# 03_02_MCU_STM32F103.net
KiCad netlist of a schematic drawn in Altium Designer
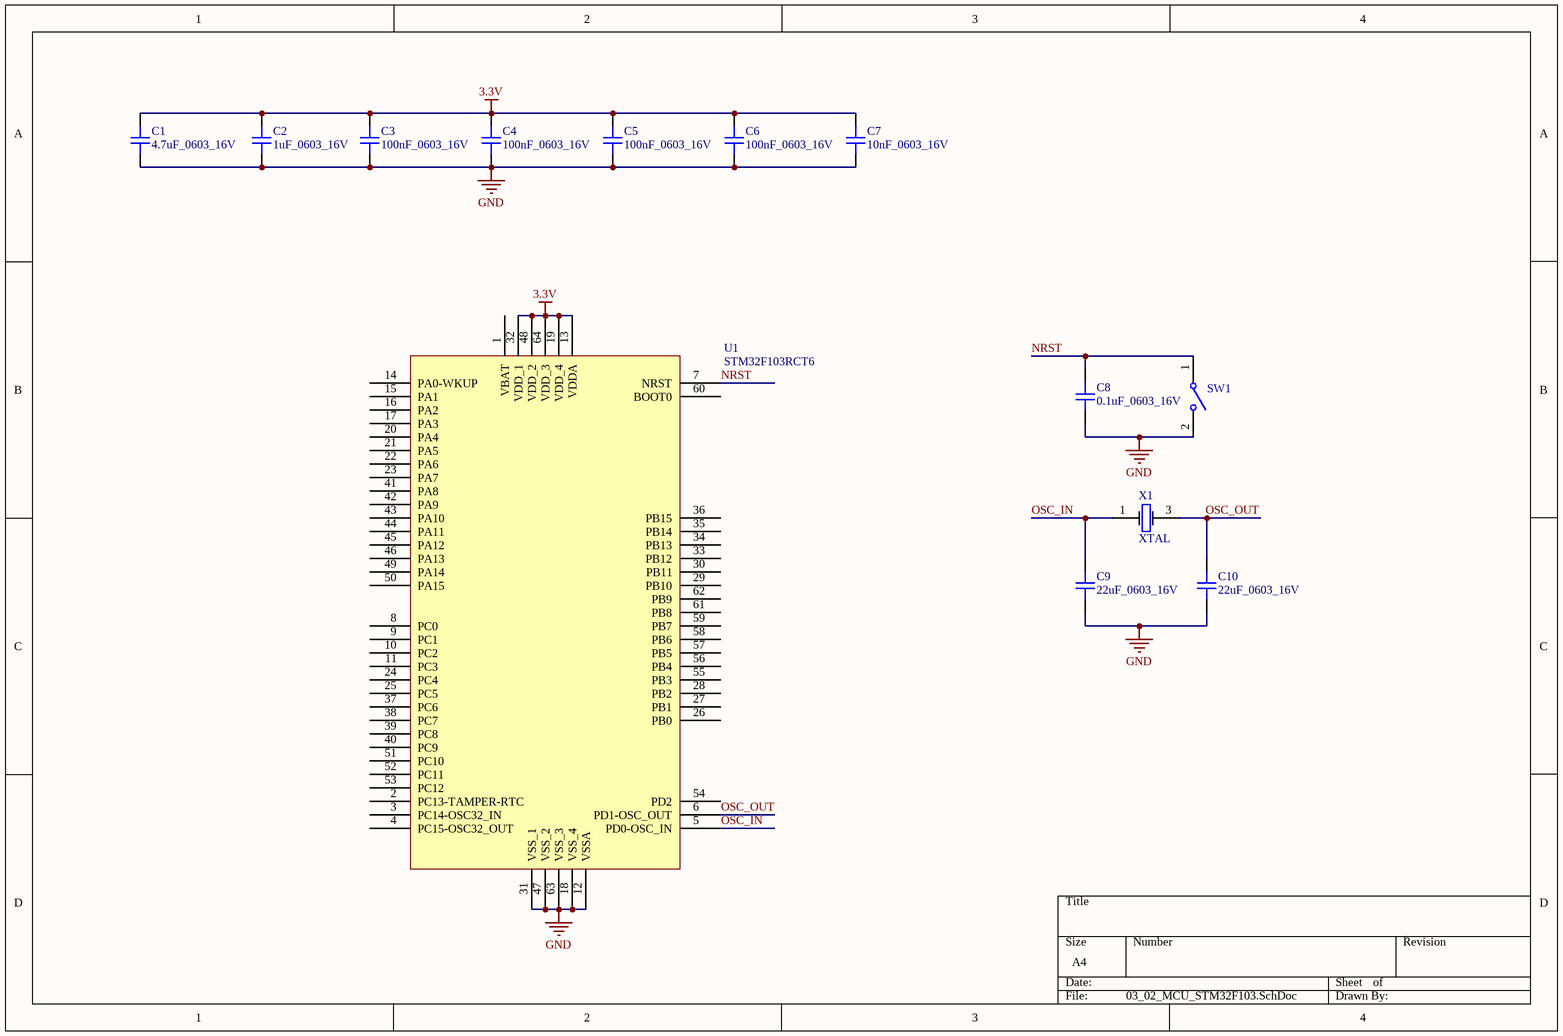
[diagram p0: 03_02_MCU_STM32F103.SchDoc]

(export (version "E")
  (design (tool "Eeschema 10.0.6"))
  (components
    (comp (ref "C1")
      (value "4.7uF_0603_16V")
      (footprint "CAP_0603")
      (description "Capacitor SMD 0603 16V")
      (libsource (lib "Lib-PhilsLab") (part "CAP_0603_16V"))
    )
    (comp (ref "C2")
      (value "1uF_0603_16V")
      (footprint "CAP_0603")
      (description "Capacitor SMD 0603 16V")
      (libsource (lib "Lib-PhilsLab") (part "CAP_0603_16V"))
    )
    (comp (ref "C3")
      (value "100nF_0603_16V")
      (footprint "CAP_0603")
      (description "Capacitor SMD 0603 16V")
      (libsource (lib "Lib-PhilsLab") (part "CAP_0603_16V"))
    )
    (comp (ref "C4")
      (value "100nF_0603_16V")
      (footprint "CAP_0603")
      (description "Capacitor SMD 0603 16V")
      (libsource (lib "Lib-PhilsLab") (part "CAP_0603_16V"))
    )
    (comp (ref "C5")
      (value "100nF_0603_16V")
      (footprint "CAP_0603")
      (description "Capacitor SMD 0603 16V")
      (libsource (lib "Lib-PhilsLab") (part "CAP_0603_16V"))
    )
    (comp (ref "C6")
      (value "100nF_0603_16V")
      (footprint "CAP_0603")
      (description "Capacitor SMD 0603 16V")
      (libsource (lib "Lib-PhilsLab") (part "CAP_0603_16V"))
    )
    (comp (ref "C7")
      (value "10nF_0603_16V")
      (footprint "CAP_0603")
      (description "Capacitor SMD 0603 16V")
      (libsource (lib "Lib-PhilsLab") (part "CAP_0603_16V"))
    )
    (comp (ref "C8")
      (value "0.1uF_0603_16V")
      (footprint "CAP_0603")
      (description "Capacitor SMD 0603 16V")
      (libsource (lib "Lib-PhilsLab") (part "CAP_0603_16V"))
    )
    (comp (ref "C9")
      (value "22uF_0603_16V")
      (footprint "CAP_0603")
      (description "Capacitor SMD 0603 16V")
      (libsource (lib "Lib-PhilsLab") (part "CAP_0603_16V"))
    )
    (comp (ref "C10")
      (value "22uF_0603_16V")
      (footprint "CAP_0603")
      (description "Capacitor SMD 0603 16V")
      (libsource (lib "Lib-PhilsLab") (part "CAP_0603_16V"))
    )
    (comp (ref "SW1")
      (value "434121025816")
      (footprint "WS-TASV_L6W3.8H2.5_4341x10258x6")
      (description "WS-TASV SMT Tact Switch, 12VDC, 50mA, 160g, height 2.5mm")
      (fields (field (name "MANUFACTURER") "Wurth Elektronik"))
      (libsource (lib "Altium_WS-TASV (rev22a)") (part "434121025816"))
    )
    (comp (ref "U1")
      (value "STM32F103RCT6")
      (footprint "STM32F103RCT6")
      (fields (field (name "MFR") "STMicroelectronics"))
      (libsource (lib "Giang's Libs") (part "STM32F103RCT6"))
    )
    (comp (ref "X1") (value "XTAL") (footprint "XTAL 3225") (libsource (lib "MiclsLib") (part "XTAL")))
  )
  (nets
    (net (code "1") (name "/NRST") (class "Default")
      (node (ref "C8") (pin "2") (pinfunction "2_2") (pintype "passive"))
      (node (ref "SW1") (pin "1") (pinfunction "1_1") (pintype "passive"))
      (node (ref "U1") (pin "7") (pinfunction "NRST_7") (pintype "passive"))
    )
    (net (code "2") (name "/OSC_IN") (class "Default")
      (node (ref "C9") (pin "2") (pinfunction "2_2") (pintype "passive"))
      (node (ref "U1") (pin "5") (pinfunction "PD0-OSC_IN_5") (pintype "passive"))
      (node (ref "X1") (pin "1") (pinfunction "8_1") (pintype "passive"))
    )
    (net (code "3") (name "/OSC_OUT") (class "Default")
      (node (ref "C10") (pin "2") (pinfunction "2_2") (pintype "passive"))
      (node (ref "U1") (pin "6") (pinfunction "PD1-OSC_OUT_6") (pintype "passive"))
      (node (ref "X1") (pin "3") (pinfunction "9_3") (pintype "passive"))
    )
    (net (code "4") (name "3.3V") (class "Default")
      (node (ref "C1") (pin "2") (pinfunction "2_2") (pintype "passive"))
      (node (ref "C2") (pin "2") (pinfunction "2_2") (pintype "passive"))
      (node (ref "C3") (pin "2") (pinfunction "2_2") (pintype "passive"))
      (node (ref "C4") (pin "2") (pinfunction "2_2") (pintype "passive"))
      (node (ref "C5") (pin "2") (pinfunction "2_2") (pintype "passive"))
      (node (ref "C6") (pin "2") (pinfunction "2_2") (pintype "passive"))
      (node (ref "C7") (pin "2") (pinfunction "2_2") (pintype "passive"))
      (node (ref "U1") (pin "13") (pinfunction "VDDA_13") (pintype "passive"))
      (node (ref "U1") (pin "19") (pinfunction "VDD_4_19") (pintype "passive"))
      (node (ref "U1") (pin "32") (pinfunction "VDD_1_32") (pintype "passive"))
      (node (ref "U1") (pin "48") (pinfunction "VDD_2_48") (pintype "passive"))
      (node (ref "U1") (pin "64") (pinfunction "VDD_3_64") (pintype "passive"))
    )
    (net (code "5") (name "GND") (class "Default")
      (node (ref "C1") (pin "1") (pinfunction "1_1") (pintype "passive"))
      (node (ref "C10") (pin "1") (pinfunction "1_1") (pintype "passive"))
      (node (ref "C2") (pin "1") (pinfunction "1_1") (pintype "passive"))
      (node (ref "C3") (pin "1") (pinfunction "1_1") (pintype "passive"))
      (node (ref "C4") (pin "1") (pinfunction "1_1") (pintype "passive"))
      (node (ref "C5") (pin "1") (pinfunction "1_1") (pintype "passive"))
      (node (ref "C6") (pin "1") (pinfunction "1_1") (pintype "passive"))
      (node (ref "C7") (pin "1") (pinfunction "1_1") (pintype "passive"))
      (node (ref "C8") (pin "1") (pinfunction "1_1") (pintype "passive"))
      (node (ref "C9") (pin "1") (pinfunction "1_1") (pintype "passive"))
      (node (ref "SW1") (pin "2") (pinfunction "2_2") (pintype "passive"))
      (node (ref "U1") (pin "12") (pinfunction "VSSA_12") (pintype "passive"))
      (node (ref "U1") (pin "18") (pinfunction "VSS_4_18") (pintype "passive"))
      (node (ref "U1") (pin "31") (pinfunction "VSS_1_31") (pintype "passive"))
      (node (ref "U1") (pin "47") (pinfunction "VSS_2_47") (pintype "passive"))
      (node (ref "U1") (pin "63") (pinfunction "VSS_3_63") (pintype "passive"))
    )
    (net (code "6") (name "unconnected-(U1-BOOT0-Pad60)") (class "Default")
      (node (ref "U1") (pin "60") (pinfunction "BOOT0_60") (pintype "passive"))
    )
    (net (code "7") (name "unconnected-(U1-PA0-WKUP-Pad14)") (class "Default")
      (node (ref "U1") (pin "14") (pinfunction "PA0-WKUP_14") (pintype "passive"))
    )
    (net (code "8") (name "unconnected-(U1-PA1-Pad15)") (class "Default")
      (node (ref "U1") (pin "15") (pinfunction "PA1_15") (pintype "passive"))
    )
    (net (code "9") (name "unconnected-(U1-PA2-Pad16)") (class "Default")
      (node (ref "U1") (pin "16") (pinfunction "PA2_16") (pintype "passive"))
    )
    (net (code "10") (name "unconnected-(U1-PA3-Pad17)") (class "Default")
      (node (ref "U1") (pin "17") (pinfunction "PA3_17") (pintype "passive"))
    )
    (net (code "11") (name "unconnected-(U1-PA4-Pad20)") (class "Default")
      (node (ref "U1") (pin "20") (pinfunction "PA4_20") (pintype "passive"))
    )
    (net (code "12") (name "unconnected-(U1-PA5-Pad21)") (class "Default")
      (node (ref "U1") (pin "21") (pinfunction "PA5_21") (pintype "passive"))
    )
    (net (code "13") (name "unconnected-(U1-PA6-Pad22)") (class "Default")
      (node (ref "U1") (pin "22") (pinfunction "PA6_22") (pintype "passive"))
    )
    (net (code "14") (name "unconnected-(U1-PA7-Pad23)") (class "Default")
      (node (ref "U1") (pin "23") (pinfunction "PA7_23") (pintype "passive"))
    )
    (net (code "15") (name "unconnected-(U1-PA8-Pad41)") (class "Default")
      (node (ref "U1") (pin "41") (pinfunction "PA8_41") (pintype "passive"))
    )
    (net (code "16") (name "unconnected-(U1-PA9-Pad42)") (class "Default")
      (node (ref "U1") (pin "42") (pinfunction "PA9_42") (pintype "passive"))
    )
    (net (code "17") (name "unconnected-(U1-PA10-Pad43)") (class "Default")
      (node (ref "U1") (pin "43") (pinfunction "PA10_43") (pintype "passive"))
    )
    (net (code "18") (name "unconnected-(U1-PA11-Pad44)") (class "Default")
      (node (ref "U1") (pin "44") (pinfunction "PA11_44") (pintype "passive"))
    )
    (net (code "19") (name "unconnected-(U1-PA12-Pad45)") (class "Default")
      (node (ref "U1") (pin "45") (pinfunction "PA12_45") (pintype "passive"))
    )
    (net (code "20") (name "unconnected-(U1-PA13-Pad46)") (class "Default")
      (node (ref "U1") (pin "46") (pinfunction "PA13_46") (pintype "passive"))
    )
    (net (code "21") (name "unconnected-(U1-PA14-Pad49)") (class "Default")
      (node (ref "U1") (pin "49") (pinfunction "PA14_49") (pintype "passive"))
    )
    (net (code "22") (name "unconnected-(U1-PA15-Pad50)") (class "Default")
      (node (ref "U1") (pin "50") (pinfunction "PA15_50") (pintype "passive"))
    )
    (net (code "23") (name "unconnected-(U1-PB0-Pad26)") (class "Default")
      (node (ref "U1") (pin "26") (pinfunction "PB0_26") (pintype "passive"))
    )
    (net (code "24") (name "unconnected-(U1-PB1-Pad27)") (class "Default")
      (node (ref "U1") (pin "27") (pinfunction "PB1_27") (pintype "passive"))
    )
    (net (code "25") (name "unconnected-(U1-PB2-Pad28)") (class "Default")
      (node (ref "U1") (pin "28") (pinfunction "PB2_28") (pintype "passive"))
    )
    (net (code "26") (name "unconnected-(U1-PB3-Pad55)") (class "Default")
      (node (ref "U1") (pin "55") (pinfunction "PB3_55") (pintype "passive"))
    )
    (net (code "27") (name "unconnected-(U1-PB4-Pad56)") (class "Default")
      (node (ref "U1") (pin "56") (pinfunction "PB4_56") (pintype "passive"))
    )
    (net (code "28") (name "unconnected-(U1-PB5-Pad57)") (class "Default")
      (node (ref "U1") (pin "57") (pinfunction "PB5_57") (pintype "passive"))
    )
    (net (code "29") (name "unconnected-(U1-PB6-Pad58)") (class "Default")
      (node (ref "U1") (pin "58") (pinfunction "PB6_58") (pintype "passive"))
    )
    (net (code "30") (name "unconnected-(U1-PB7-Pad59)") (class "Default")
      (node (ref "U1") (pin "59") (pinfunction "PB7_59") (pintype "passive"))
    )
    (net (code "31") (name "unconnected-(U1-PB8-Pad61)") (class "Default")
      (node (ref "U1") (pin "61") (pinfunction "PB8_61") (pintype "passive"))
    )
    (net (code "32") (name "unconnected-(U1-PB9-Pad62)") (class "Default")
      (node (ref "U1") (pin "62") (pinfunction "PB9_62") (pintype "passive"))
    )
    (net (code "33") (name "unconnected-(U1-PB10-Pad29)") (class "Default")
      (node (ref "U1") (pin "29") (pinfunction "PB10_29") (pintype "passive"))
    )
    (net (code "34") (name "unconnected-(U1-PB11-Pad30)") (class "Default")
      (node (ref "U1") (pin "30") (pinfunction "PB11_30") (pintype "passive"))
    )
    (net (code "35") (name "unconnected-(U1-PB12-Pad33)") (class "Default")
      (node (ref "U1") (pin "33") (pinfunction "PB12_33") (pintype "passive"))
    )
    (net (code "36") (name "unconnected-(U1-PB13-Pad34)") (class "Default")
      (node (ref "U1") (pin "34") (pinfunction "PB13_34") (pintype "passive"))
    )
    (net (code "37") (name "unconnected-(U1-PB14-Pad35)") (class "Default")
      (node (ref "U1") (pin "35") (pinfunction "PB14_35") (pintype "passive"))
    )
    (net (code "38") (name "unconnected-(U1-PB15-Pad36)") (class "Default")
      (node (ref "U1") (pin "36") (pinfunction "PB15_36") (pintype "passive"))
    )
    (net (code "39") (name "unconnected-(U1-PC0-Pad8)") (class "Default")
      (node (ref "U1") (pin "8") (pinfunction "PC0_8") (pintype "passive"))
    )
    (net (code "40") (name "unconnected-(U1-PC1-Pad9)") (class "Default")
      (node (ref "U1") (pin "9") (pinfunction "PC1_9") (pintype "passive"))
    )
    (net (code "41") (name "unconnected-(U1-PC2-Pad10)") (class "Default")
      (node (ref "U1") (pin "10") (pinfunction "PC2_10") (pintype "passive"))
    )
    (net (code "42") (name "unconnected-(U1-PC3-Pad11)") (class "Default")
      (node (ref "U1") (pin "11") (pinfunction "PC3_11") (pintype "passive"))
    )
    (net (code "43") (name "unconnected-(U1-PC4-Pad24)") (class "Default")
      (node (ref "U1") (pin "24") (pinfunction "PC4_24") (pintype "passive"))
    )
    (net (code "44") (name "unconnected-(U1-PC5-Pad25)") (class "Default")
      (node (ref "U1") (pin "25") (pinfunction "PC5_25") (pintype "passive"))
    )
    (net (code "45") (name "unconnected-(U1-PC6-Pad37)") (class "Default")
      (node (ref "U1") (pin "37") (pinfunction "PC6_37") (pintype "passive"))
    )
    (net (code "46") (name "unconnected-(U1-PC7-Pad38)") (class "Default")
      (node (ref "U1") (pin "38") (pinfunction "PC7_38") (pintype "passive"))
    )
    (net (code "47") (name "unconnected-(U1-PC8-Pad39)") (class "Default")
      (node (ref "U1") (pin "39") (pinfunction "PC8_39") (pintype "passive"))
    )
    (net (code "48") (name "unconnected-(U1-PC9-Pad40)") (class "Default")
      (node (ref "U1") (pin "40") (pinfunction "PC9_40") (pintype "passive"))
    )
    (net (code "49") (name "unconnected-(U1-PC10-Pad51)") (class "Default")
      (node (ref "U1") (pin "51") (pinfunction "PC10_51") (pintype "passive"))
    )
    (net (code "50") (name "unconnected-(U1-PC11-Pad52)") (class "Default")
      (node (ref "U1") (pin "52") (pinfunction "PC11_52") (pintype "passive"))
    )
    (net (code "51") (name "unconnected-(U1-PC12-Pad53)") (class "Default")
      (node (ref "U1") (pin "53") (pinfunction "PC12_53") (pintype "passive"))
    )
    (net (code "52") (name "unconnected-(U1-PC13-TAMPER-RTC-Pad2)") (class "Default")
      (node (ref "U1") (pin "2") (pinfunction "PC13-TAMPER-RTC_2") (pintype "passive"))
    )
    (net (code "53") (name "unconnected-(U1-PC14-OSC32_IN-Pad3)") (class "Default")
      (node (ref "U1") (pin "3") (pinfunction "PC14-OSC32_IN_3") (pintype "passive"))
    )
    (net (code "54") (name "unconnected-(U1-PC15-OSC32_OUT-Pad4)") (class "Default")
      (node (ref "U1") (pin "4") (pinfunction "PC15-OSC32_OUT_4") (pintype "passive"))
    )
    (net (code "55") (name "unconnected-(U1-PD2-Pad54)") (class "Default")
      (node (ref "U1") (pin "54") (pinfunction "PD2_54") (pintype "passive"))
    )
    (net (code "56") (name "unconnected-(U1-VBAT-Pad1)") (class "Default")
      (node (ref "U1") (pin "1") (pinfunction "VBAT_1") (pintype "passive"))
    )
  )
)
